# PCB_Instrumenta_o_v2.net
KiCad netlist of a schematic drawn in EAGLE
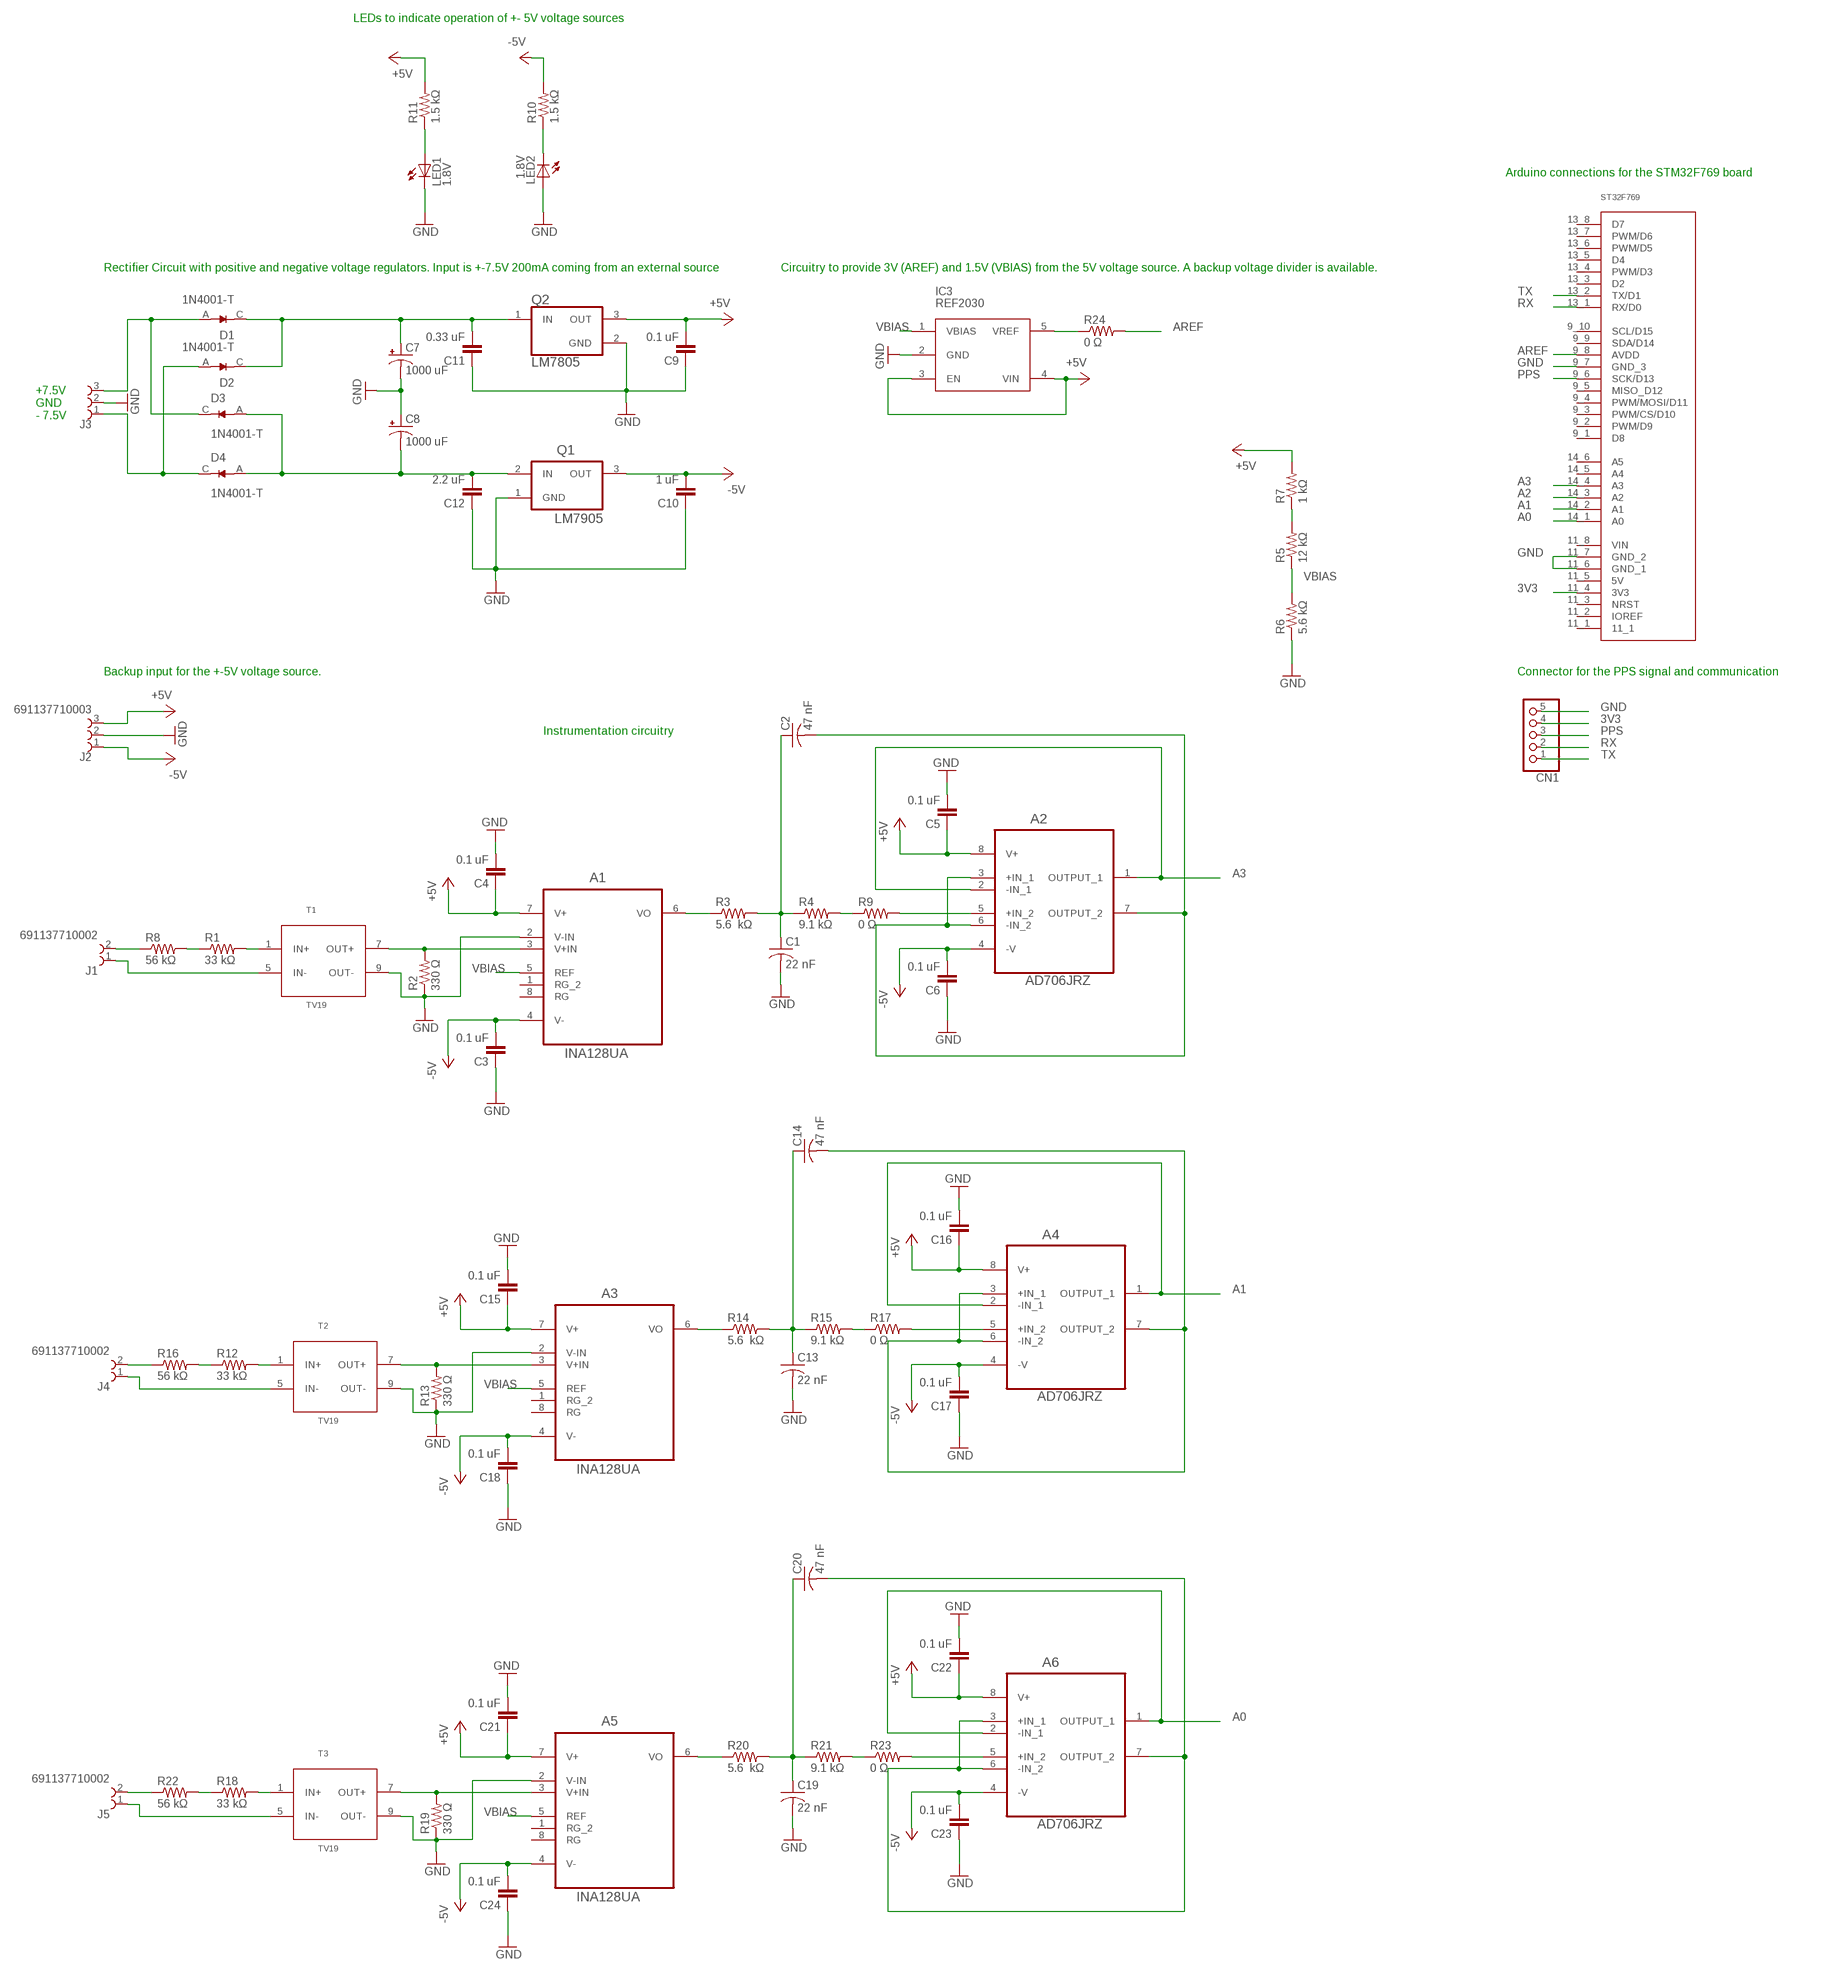
[diagram p0: schematic, sheet 1]

(export (version "E")
  (design (tool "Eeschema 10.0.6"))
  (components
    (comp (ref "A1")
      (value "INA128UA")
      (footprint "eagle-import:SOIC127P600X175-8N")
      (fields (field (name "MF") "Texas"))
      (libsource (lib "eagle-import") (part "INA128UA"))
    )
    (comp (ref "A2")
      (value "AD706JRZ")
      (footprint "eagle-import:SOIC127P600X175-8N")
      (fields (field (name "MF") "Analog Devices") (field (name "MP") "AD706JRZ-REEL7"))
      (libsource (lib "eagle-import") (part "AD706JRZ-REEL-REEL7"))
    )
    (comp (ref "A3")
      (value "INA128UA")
      (footprint "eagle-import:SOIC127P600X175-8N")
      (fields (field (name "MF") "Texas"))
      (libsource (lib "eagle-import") (part "INA128UA"))
    )
    (comp (ref "A4")
      (value "AD706JRZ")
      (footprint "eagle-import:SOIC127P600X175-8N")
      (fields (field (name "MF") "Analog Devices") (field (name "MP") "AD706JRZ-REEL7"))
      (libsource (lib "eagle-import") (part "AD706JRZ-REEL-REEL7"))
    )
    (comp (ref "A5")
      (value "INA128UA")
      (footprint "eagle-import:SOIC127P600X175-8N")
      (fields (field (name "MF") "Texas"))
      (libsource (lib "eagle-import") (part "INA128UA"))
    )
    (comp (ref "A6")
      (value "AD706JRZ")
      (footprint "eagle-import:SOIC127P600X175-8N")
      (fields (field (name "MF") "Analog Devices") (field (name "MP") "AD706JRZ-REEL7"))
      (libsource (lib "eagle-import") (part "AD706JRZ-REEL-REEL7"))
    )
    (comp (ref "C1")
      (value "22 nF")
      (footprint "eagle-import:C1206")
      (libsource (lib "eagle-import") (part "C-USC1206"))
    )
    (comp (ref "C2")
      (value "47 nF")
      (footprint "eagle-import:C1206")
      (libsource (lib "eagle-import") (part "C-USC1206"))
    )
    (comp (ref "C3")
      (value "0.1 uF")
      (footprint "eagle-import:C0805")
      (libsource (lib "eagle-import") (part "C-EUC0805"))
    )
    (comp (ref "C4")
      (value "0.1 uF")
      (footprint "eagle-import:C0805")
      (libsource (lib "eagle-import") (part "C-EUC0805"))
    )
    (comp (ref "C5")
      (value "0.1 uF")
      (footprint "eagle-import:C0805")
      (libsource (lib "eagle-import") (part "C-EUC0805"))
    )
    (comp (ref "C6")
      (value "0.1 uF")
      (footprint "eagle-import:C0805")
      (libsource (lib "eagle-import") (part "C-EUC0805"))
    )
    (comp (ref "C7")
      (value "1000 uF")
      (footprint "eagle-import:E5-10,5")
      (libsource (lib "eagle-import") (part "CPOL-USE5-10.5"))
    )
    (comp (ref "C8")
      (value "1000 uF")
      (footprint "eagle-import:E5-10,5")
      (libsource (lib "eagle-import") (part "CPOL-USE5-10.5"))
    )
    (comp (ref "C9")
      (value "0.1 uF")
      (footprint "eagle-import:C0805")
      (libsource (lib "eagle-import") (part "C-EUC0805"))
    )
    (comp (ref "C10")
      (value "1 uF")
      (footprint "eagle-import:C0805")
      (libsource (lib "eagle-import") (part "C-EUC0805"))
    )
    (comp (ref "C11")
      (value "0.33 uF")
      (footprint "eagle-import:C0805")
      (libsource (lib "eagle-import") (part "C-EUC0805"))
    )
    (comp (ref "C12")
      (value "2.2 uF")
      (footprint "eagle-import:C0805")
      (libsource (lib "eagle-import") (part "C-EUC0805"))
    )
    (comp (ref "C13")
      (value "22 nF")
      (footprint "eagle-import:C1206")
      (libsource (lib "eagle-import") (part "C-USC1206"))
    )
    (comp (ref "C14")
      (value "47 nF")
      (footprint "eagle-import:C1206")
      (libsource (lib "eagle-import") (part "C-USC1206"))
    )
    (comp (ref "C15")
      (value "0.1 uF")
      (footprint "eagle-import:C0805")
      (libsource (lib "eagle-import") (part "C-EUC0805"))
    )
    (comp (ref "C16")
      (value "0.1 uF")
      (footprint "eagle-import:C0805")
      (libsource (lib "eagle-import") (part "C-EUC0805"))
    )
    (comp (ref "C17")
      (value "0.1 uF")
      (footprint "eagle-import:C0805")
      (libsource (lib "eagle-import") (part "C-EUC0805"))
    )
    (comp (ref "C18")
      (value "0.1 uF")
      (footprint "eagle-import:C0805")
      (libsource (lib "eagle-import") (part "C-EUC0805"))
    )
    (comp (ref "C19")
      (value "22 nF")
      (footprint "eagle-import:C1206")
      (libsource (lib "eagle-import") (part "C-USC1206"))
    )
    (comp (ref "C20")
      (value "47 nF")
      (footprint "eagle-import:C1206")
      (libsource (lib "eagle-import") (part "C-USC1206"))
    )
    (comp (ref "C21")
      (value "0.1 uF")
      (footprint "eagle-import:C0805")
      (libsource (lib "eagle-import") (part "C-EUC0805"))
    )
    (comp (ref "C22")
      (value "0.1 uF")
      (footprint "eagle-import:C0805")
      (libsource (lib "eagle-import") (part "C-EUC0805"))
    )
    (comp (ref "C23")
      (value "0.1 uF")
      (footprint "eagle-import:C0805")
      (libsource (lib "eagle-import") (part "C-EUC0805"))
    )
    (comp (ref "C24")
      (value "0.1 uF")
      (footprint "eagle-import:C0805")
      (libsource (lib "eagle-import") (part "C-EUC0805"))
    )
    (comp (ref "CN1")
      (value "PINHD-1X5")
      (footprint "eagle-import:1X05")
      (libsource (lib "eagle-import") (part "PINHD-1X5"))
    )
    (comp (ref "D1")
      (value "1N4001-T")
      (footprint "eagle-import:DIOAD953W69L521D272")
      (fields (field (name "MF") "ON Semiconductor") (field (name "MP") "1N4001"))
      (libsource (lib "eagle-import") (part "1N4001-T"))
    )
    (comp (ref "D2")
      (value "1N4001-T")
      (footprint "eagle-import:DIOAD953W69L521D272")
      (fields (field (name "MF") "ON Semiconductor") (field (name "MP") "1N4001"))
      (libsource (lib "eagle-import") (part "1N4001-T"))
    )
    (comp (ref "D3")
      (value "1N4001-T")
      (footprint "eagle-import:DIOAD953W69L521D272")
      (fields (field (name "MF") "ON Semiconductor") (field (name "MP") "1N4001"))
      (libsource (lib "eagle-import") (part "1N4001-T"))
    )
    (comp (ref "D4")
      (value "1N4001-T")
      (footprint "eagle-import:DIOAD953W69L521D272")
      (fields (field (name "MF") "ON Semiconductor") (field (name "MP") "1N4001"))
      (libsource (lib "eagle-import") (part "1N4001-T"))
    )
    (comp (ref "IC3")
      (value "REF2030")
      (footprint "eagle-import:TSOT-23_S5")
      (libsource (lib "eagle-import") (part "REF2030"))
    )
    (comp (ref "J1")
      (value "691137710002")
      (footprint "eagle-import:691137710002")
      (fields (field (name "MF") "Wurth Electronics"))
      (libsource (lib "eagle-import") (part "691137710002"))
    )
    (comp (ref "J2")
      (value "691137710003")
      (footprint "eagle-import:691137710003")
      (fields (field (name "MF") "Wurth Electronics"))
      (libsource (lib "eagle-import") (part "691137710003"))
    )
    (comp (ref "J3")
      (value "691137710003")
      (footprint "eagle-import:691137710003")
      (fields (field (name "MF") "Wurth Electronics"))
      (libsource (lib "eagle-import") (part "691137710003"))
    )
    (comp (ref "J4")
      (value "691137710002")
      (footprint "eagle-import:691137710002")
      (fields (field (name "MF") "Wurth Electronics"))
      (libsource (lib "eagle-import") (part "691137710002"))
    )
    (comp (ref "J5")
      (value "691137710002")
      (footprint "eagle-import:691137710002")
      (fields (field (name "MF") "Wurth Electronics"))
      (libsource (lib "eagle-import") (part "691137710002"))
    )
    (comp (ref "LED1")
      (value "1.8V")
      (footprint "eagle-import:LED5MM")
      (libsource (lib "eagle-import") (part "my_led_LED5MM"))
    )
    (comp (ref "LED2")
      (value "1.8V")
      (footprint "eagle-import:LED5MM")
      (libsource (lib "eagle-import") (part "LED5MM"))
    )
    (comp (ref "Q1")
      (value "LM7905")
      (footprint "eagle-import:TO254P450X1020X1935-3P")
      (fields (field (name "MF") "STMicroelectronics") (field (name "MP") "L7905ACV"))
      (libsource (lib "eagle-import") (part "L7905ACV"))
    )
    (comp (ref "Q2")
      (value "LM7805")
      (footprint "eagle-import:TO254P1054X470X2600-3")
      (fields (field (name "MF") "ON Semiconductor") (field (name "MP") "LM7805CT"))
      (libsource (lib "eagle-import") (part "LM7805CT/NOPB"))
    )
    (comp (ref "R1")
      (value "33 kΩ")
      (footprint "eagle-import:0207_7")
      (libsource (lib "eagle-import") (part "R-US_0207/7"))
    )
    (comp (ref "R2")
      (value "330 Ω")
      (footprint "eagle-import:0207_7")
      (libsource (lib "eagle-import") (part "R-US_0207/7"))
    )
    (comp (ref "R3")
      (value "5.6 kΩ")
      (footprint "eagle-import:R1206")
      (libsource (lib "eagle-import") (part "resistor_348_R-US_R1206"))
    )
    (comp (ref "R4")
      (value "9.1 kΩ")
      (footprint "eagle-import:R1206")
      (libsource (lib "eagle-import") (part "resistor_348_R-US_R1206"))
    )
    (comp (ref "R5")
      (value "12 kΩ")
      (footprint "eagle-import:R1206")
      (libsource (lib "eagle-import") (part "resistor_348_R-US_R1206"))
    )
    (comp (ref "R6")
      (value "5.6 kΩ")
      (footprint "eagle-import:R1206")
      (libsource (lib "eagle-import") (part "resistor_348_R-US_R1206"))
    )
    (comp (ref "R7")
      (value "1 kΩ")
      (footprint "eagle-import:R1206")
      (libsource (lib "eagle-import") (part "resistor_348_R-US_R1206"))
    )
    (comp (ref "R8")
      (value "56 kΩ")
      (footprint "eagle-import:0207_7")
      (libsource (lib "eagle-import") (part "R-US_0207/7"))
    )
    (comp (ref "R9")
      (value "0 Ω")
      (footprint "eagle-import:R1206")
      (libsource (lib "eagle-import") (part "resistor_348_R-US_R1206"))
    )
    (comp (ref "R10")
      (value "1.5 kΩ")
      (footprint "eagle-import:R1206")
      (libsource (lib "eagle-import") (part "resistor_348_R-US_R1206"))
    )
    (comp (ref "R11")
      (value "1.5 kΩ")
      (footprint "eagle-import:R1206")
      (libsource (lib "eagle-import") (part "resistor_348_R-US_R1206"))
    )
    (comp (ref "R12")
      (value "33 kΩ")
      (footprint "eagle-import:0207_7")
      (libsource (lib "eagle-import") (part "R-US_0207/7"))
    )
    (comp (ref "R13")
      (value "330 Ω")
      (footprint "eagle-import:0207_7")
      (libsource (lib "eagle-import") (part "R-US_0207/7"))
    )
    (comp (ref "R14")
      (value "5.6 kΩ")
      (footprint "eagle-import:R1206")
      (libsource (lib "eagle-import") (part "resistor_348_R-US_R1206"))
    )
    (comp (ref "R15")
      (value "9.1 kΩ")
      (footprint "eagle-import:R1206")
      (libsource (lib "eagle-import") (part "resistor_348_R-US_R1206"))
    )
    (comp (ref "R16")
      (value "56 kΩ")
      (footprint "eagle-import:0207_7")
      (libsource (lib "eagle-import") (part "R-US_0207/7"))
    )
    (comp (ref "R17")
      (value "0 Ω")
      (footprint "eagle-import:R1206")
      (libsource (lib "eagle-import") (part "resistor_348_R-US_R1206"))
    )
    (comp (ref "R18")
      (value "33 kΩ")
      (footprint "eagle-import:0207_7")
      (libsource (lib "eagle-import") (part "R-US_0207/7"))
    )
    (comp (ref "R19")
      (value "330 Ω")
      (footprint "eagle-import:0207_7")
      (libsource (lib "eagle-import") (part "R-US_0207/7"))
    )
    (comp (ref "R20")
      (value "5.6 kΩ")
      (footprint "eagle-import:R1206")
      (libsource (lib "eagle-import") (part "resistor_348_R-US_R1206"))
    )
    (comp (ref "R21")
      (value "9.1 kΩ")
      (footprint "eagle-import:R1206")
      (libsource (lib "eagle-import") (part "resistor_348_R-US_R1206"))
    )
    (comp (ref "R22")
      (value "56 kΩ")
      (footprint "eagle-import:0207_7")
      (libsource (lib "eagle-import") (part "R-US_0207/7"))
    )
    (comp (ref "R23")
      (value "0 Ω")
      (footprint "eagle-import:R1206")
      (libsource (lib "eagle-import") (part "resistor_348_R-US_R1206"))
    )
    (comp (ref "R24")
      (value "0 Ω")
      (footprint "eagle-import:R1206")
      (libsource (lib "eagle-import") (part "resistor_348_R-US_R1206"))
    )
    (comp (ref "T1")
      (value "TV19")
      (footprint "eagle-import:TV19")
      (libsource (lib "eagle-import") (part "TV19"))
    )
    (comp (ref "T2")
      (value "TV19")
      (footprint "eagle-import:TV19")
      (libsource (lib "eagle-import") (part "TV19"))
    )
    (comp (ref "T3")
      (value "TV19")
      (footprint "eagle-import:TV19")
      (libsource (lib "eagle-import") (part "TV19"))
    )
    (comp (ref "U$1")
      (value "ST32F769")
      (footprint "eagle-import:ST32F769")
      (libsource (lib "eagle-import") (part "ST32F769"))
    )
  )
  (nets
    (net (code "1") (name "+5V") (class "Default")
      (node (ref "A1") (pin "7") (pinfunction "V+_7") (pintype "power_in"))
      (node (ref "A2") (pin "8") (pinfunction "V+_8") (pintype "power_in"))
      (node (ref "A3") (pin "7") (pinfunction "V+_7") (pintype "power_in"))
      (node (ref "A4") (pin "8") (pinfunction "V+_8") (pintype "power_in"))
      (node (ref "A5") (pin "7") (pinfunction "V+_7") (pintype "power_in"))
      (node (ref "A6") (pin "8") (pinfunction "V+_8") (pintype "power_in"))
      (node (ref "C15") (pin "1") (pinfunction "1_1") (pintype "passive"))
      (node (ref "C16") (pin "1") (pinfunction "1_1") (pintype "passive"))
      (node (ref "C21") (pin "1") (pinfunction "1_1") (pintype "passive"))
      (node (ref "C22") (pin "1") (pinfunction "1_1") (pintype "passive"))
      (node (ref "C4") (pin "1") (pinfunction "1_1") (pintype "passive"))
      (node (ref "C5") (pin "1") (pinfunction "1_1") (pintype "passive"))
      (node (ref "C9") (pin "2") (pinfunction "2_2") (pintype "passive"))
      (node (ref "IC3") (pin "3") (pinfunction "EN_3") (pintype "bidirectional"))
      (node (ref "IC3") (pin "4") (pinfunction "VIN_4") (pintype "bidirectional"))
      (node (ref "J2") (pin "3") (pinfunction "3_3") (pintype "passive"))
      (node (ref "Q2") (pin "3") (pinfunction "OUT_3") (pintype "output"))
      (node (ref "R11") (pin "2") (pinfunction "2_2") (pintype "passive"))
      (node (ref "R7") (pin "2") (pinfunction "2_2") (pintype "passive"))
    )
    (net (code "2") (name "-5V") (class "Default")
      (node (ref "A1") (pin "4") (pinfunction "V-_4") (pintype "power_in"))
      (node (ref "A2") (pin "4") (pinfunction "-V_4") (pintype "power_in"))
      (node (ref "A3") (pin "4") (pinfunction "V-_4") (pintype "power_in"))
      (node (ref "A4") (pin "4") (pinfunction "-V_4") (pintype "power_in"))
      (node (ref "A5") (pin "4") (pinfunction "V-_4") (pintype "power_in"))
      (node (ref "A6") (pin "4") (pinfunction "-V_4") (pintype "power_in"))
      (node (ref "C10") (pin "2") (pinfunction "2_2") (pintype "passive"))
      (node (ref "C17") (pin "2") (pinfunction "2_2") (pintype "passive"))
      (node (ref "C18") (pin "2") (pinfunction "2_2") (pintype "passive"))
      (node (ref "C23") (pin "2") (pinfunction "2_2") (pintype "passive"))
      (node (ref "C24") (pin "2") (pinfunction "2_2") (pintype "passive"))
      (node (ref "C3") (pin "2") (pinfunction "2_2") (pintype "passive"))
      (node (ref "C6") (pin "2") (pinfunction "2_2") (pintype "passive"))
      (node (ref "J2") (pin "1") (pinfunction "1_1") (pintype "passive"))
      (node (ref "Q1") (pin "3") (pinfunction "OUT_3") (pintype "output"))
      (node (ref "R10") (pin "2") (pinfunction "2_2") (pintype "passive"))
    )
    (net (code "3") (name "/3V3") (class "Default")
      (node (ref "CN1") (pin "4") (pinfunction "4_4") (pintype "passive"))
      (node (ref "U$1") (pin "11_4") (pinfunction "3V3_11_4") (pintype "bidirectional"))
    )
    (net (code "4") (name "/A0") (class "Default")
      (node (ref "A6") (pin "1") (pinfunction "OUTPUT_1_1") (pintype "output"))
      (node (ref "A6") (pin "2") (pinfunction "-IN_1_2") (pintype "input"))
      (node (ref "U$1") (pin "14_1") (pinfunction "A0_14_1") (pintype "bidirectional"))
    )
    (net (code "5") (name "/A1") (class "Default")
      (node (ref "A4") (pin "1") (pinfunction "OUTPUT_1_1") (pintype "output"))
      (node (ref "A4") (pin "2") (pinfunction "-IN_1_2") (pintype "input"))
      (node (ref "U$1") (pin "14_2") (pinfunction "A1_14_2") (pintype "bidirectional"))
    )
    (net (code "6") (name "/A2") (class "Default")
      (node (ref "U$1") (pin "14_3") (pinfunction "A2_14_3") (pintype "bidirectional"))
    )
    (net (code "7") (name "/A3") (class "Default")
      (node (ref "A2") (pin "1") (pinfunction "OUTPUT_1_1") (pintype "output"))
      (node (ref "A2") (pin "2") (pinfunction "-IN_1_2") (pintype "input"))
      (node (ref "U$1") (pin "14_4") (pinfunction "A3_14_4") (pintype "bidirectional"))
    )
    (net (code "8") (name "/AREF") (class "Default")
      (node (ref "R24") (pin "2") (pinfunction "2_2") (pintype "passive"))
      (node (ref "U$1") (pin "9_8") (pinfunction "AVDD_9_8") (pintype "bidirectional"))
    )
    (net (code "9") (name "/PPS") (class "Default")
      (node (ref "CN1") (pin "3") (pinfunction "3_3") (pintype "passive"))
      (node (ref "U$1") (pin "9_6") (pinfunction "SCK/D13_9_6") (pintype "bidirectional"))
    )
    (net (code "10") (name "/RX") (class "Default")
      (node (ref "CN1") (pin "2") (pinfunction "2_2") (pintype "passive"))
      (node (ref "U$1") (pin "13_1") (pinfunction "RX/D0_13_1") (pintype "bidirectional"))
    )
    (net (code "11") (name "/TX") (class "Default")
      (node (ref "CN1") (pin "1") (pinfunction "1_1") (pintype "passive"))
      (node (ref "U$1") (pin "13_2") (pinfunction "TX/D1_13_2") (pintype "bidirectional"))
    )
    (net (code "12") (name "/VBIAS") (class "Default")
      (node (ref "A1") (pin "5") (pinfunction "REF_5") (pintype "input"))
      (node (ref "A3") (pin "5") (pinfunction "REF_5") (pintype "input"))
      (node (ref "A5") (pin "5") (pinfunction "REF_5") (pintype "input"))
      (node (ref "IC3") (pin "1") (pinfunction "VBIAS_1") (pintype "bidirectional"))
      (node (ref "R5") (pin "1") (pinfunction "1_1") (pintype "passive"))
      (node (ref "R6") (pin "2") (pinfunction "2_2") (pintype "passive"))
    )
    (net (code "13") (name "GND") (class "Default")
      (node (ref "A1") (pin "2") (pinfunction "V-IN_2") (pintype "input"))
      (node (ref "A3") (pin "2") (pinfunction "V-IN_2") (pintype "input"))
      (node (ref "A5") (pin "2") (pinfunction "V-IN_2") (pintype "input"))
      (node (ref "C1") (pin "2") (pinfunction "2_2") (pintype "passive"))
      (node (ref "C10") (pin "1") (pinfunction "1_1") (pintype "passive"))
      (node (ref "C11") (pin "1") (pinfunction "1_1") (pintype "passive"))
      (node (ref "C12") (pin "1") (pinfunction "1_1") (pintype "passive"))
      (node (ref "C13") (pin "2") (pinfunction "2_2") (pintype "passive"))
      (node (ref "C15") (pin "2") (pinfunction "2_2") (pintype "passive"))
      (node (ref "C16") (pin "2") (pinfunction "2_2") (pintype "passive"))
      (node (ref "C17") (pin "1") (pinfunction "1_1") (pintype "passive"))
      (node (ref "C18") (pin "1") (pinfunction "1_1") (pintype "passive"))
      (node (ref "C19") (pin "2") (pinfunction "2_2") (pintype "passive"))
      (node (ref "C21") (pin "2") (pinfunction "2_2") (pintype "passive"))
      (node (ref "C22") (pin "2") (pinfunction "2_2") (pintype "passive"))
      (node (ref "C23") (pin "1") (pinfunction "1_1") (pintype "passive"))
      (node (ref "C24") (pin "1") (pinfunction "1_1") (pintype "passive"))
      (node (ref "C3") (pin "1") (pinfunction "1_1") (pintype "passive"))
      (node (ref "C4") (pin "2") (pinfunction "2_2") (pintype "passive"))
      (node (ref "C5") (pin "2") (pinfunction "2_2") (pintype "passive"))
      (node (ref "C6") (pin "1") (pinfunction "1_1") (pintype "passive"))
      (node (ref "C7") (pin "-") (pinfunction "-_-") (pintype "passive"))
      (node (ref "C8") (pin "+") (pinfunction "+_+") (pintype "passive"))
      (node (ref "C9") (pin "1") (pinfunction "1_1") (pintype "passive"))
      (node (ref "CN1") (pin "5") (pinfunction "5_5") (pintype "passive"))
      (node (ref "IC3") (pin "2") (pinfunction "GND_2") (pintype "bidirectional"))
      (node (ref "J2") (pin "2") (pinfunction "2_2") (pintype "passive"))
      (node (ref "J3") (pin "2") (pinfunction "2_2") (pintype "passive"))
      (node (ref "LED1") (pin "K") (pinfunction "C_K") (pintype "passive"))
      (node (ref "LED2") (pin "A") (pinfunction "A_A") (pintype "passive"))
      (node (ref "Q1") (pin "1") (pinfunction "GND_1") (pintype "passive"))
      (node (ref "Q2") (pin "2") (pinfunction "GND_2") (pintype "power_in"))
      (node (ref "R13") (pin "1") (pinfunction "1_1") (pintype "passive"))
      (node (ref "R19") (pin "1") (pinfunction "1_1") (pintype "passive"))
      (node (ref "R2") (pin "1") (pinfunction "1_1") (pintype "passive"))
      (node (ref "R6") (pin "1") (pinfunction "1_1") (pintype "passive"))
      (node (ref "T1") (pin "9") (pinfunction "OUT-_9") (pintype "bidirectional"))
      (node (ref "T2") (pin "9") (pinfunction "OUT-_9") (pintype "bidirectional"))
      (node (ref "T3") (pin "9") (pinfunction "OUT-_9") (pintype "bidirectional"))
      (node (ref "U$1") (pin "11_6") (pinfunction "GND_1_11_6") (pintype "bidirectional"))
      (node (ref "U$1") (pin "11_7") (pinfunction "GND_2_11_7") (pintype "bidirectional"))
      (node (ref "U$1") (pin "9_7") (pinfunction "GND_3_9_7") (pintype "bidirectional"))
    )
    (net (code "14") (name "Net-(A1-V+IN)") (class "Default")
      (node (ref "A1") (pin "3") (pinfunction "V+IN_3") (pintype "input"))
      (node (ref "R2") (pin "2") (pinfunction "2_2") (pintype "passive"))
      (node (ref "T1") (pin "7") (pinfunction "OUT+_7") (pintype "bidirectional"))
    )
    (net (code "15") (name "Net-(A1-VO)") (class "Default")
      (node (ref "A1") (pin "6") (pinfunction "VO_6") (pintype "output"))
      (node (ref "R3") (pin "1") (pinfunction "1_1") (pintype "passive"))
    )
    (net (code "16") (name "Net-(A2-+IN_1)") (class "Default")
      (node (ref "A2") (pin "3") (pinfunction "+IN_1_3") (pintype "input"))
      (node (ref "A2") (pin "6") (pinfunction "-IN_2_6") (pintype "input"))
      (node (ref "A2") (pin "7") (pinfunction "OUTPUT_2_7") (pintype "output"))
      (node (ref "C2") (pin "2") (pinfunction "2_2") (pintype "passive"))
    )
    (net (code "17") (name "Net-(A2-+IN_2)") (class "Default")
      (node (ref "A2") (pin "5") (pinfunction "+IN_2_5") (pintype "input"))
      (node (ref "R9") (pin "2") (pinfunction "2_2") (pintype "passive"))
    )
    (net (code "18") (name "Net-(A3-V+IN)") (class "Default")
      (node (ref "A3") (pin "3") (pinfunction "V+IN_3") (pintype "input"))
      (node (ref "R13") (pin "2") (pinfunction "2_2") (pintype "passive"))
      (node (ref "T2") (pin "7") (pinfunction "OUT+_7") (pintype "bidirectional"))
    )
    (net (code "19") (name "Net-(A3-VO)") (class "Default")
      (node (ref "A3") (pin "6") (pinfunction "VO_6") (pintype "output"))
      (node (ref "R14") (pin "1") (pinfunction "1_1") (pintype "passive"))
    )
    (net (code "20") (name "Net-(A4-+IN_1)") (class "Default")
      (node (ref "A4") (pin "3") (pinfunction "+IN_1_3") (pintype "input"))
      (node (ref "A4") (pin "6") (pinfunction "-IN_2_6") (pintype "input"))
      (node (ref "A4") (pin "7") (pinfunction "OUTPUT_2_7") (pintype "output"))
      (node (ref "C14") (pin "2") (pinfunction "2_2") (pintype "passive"))
    )
    (net (code "21") (name "Net-(A4-+IN_2)") (class "Default")
      (node (ref "A4") (pin "5") (pinfunction "+IN_2_5") (pintype "input"))
      (node (ref "R17") (pin "2") (pinfunction "2_2") (pintype "passive"))
    )
    (net (code "22") (name "Net-(A5-V+IN)") (class "Default")
      (node (ref "A5") (pin "3") (pinfunction "V+IN_3") (pintype "input"))
      (node (ref "R19") (pin "2") (pinfunction "2_2") (pintype "passive"))
      (node (ref "T3") (pin "7") (pinfunction "OUT+_7") (pintype "bidirectional"))
    )
    (net (code "23") (name "Net-(A5-VO)") (class "Default")
      (node (ref "A5") (pin "6") (pinfunction "VO_6") (pintype "output"))
      (node (ref "R20") (pin "1") (pinfunction "1_1") (pintype "passive"))
    )
    (net (code "24") (name "Net-(A6-+IN_1)") (class "Default")
      (node (ref "A6") (pin "3") (pinfunction "+IN_1_3") (pintype "input"))
      (node (ref "A6") (pin "6") (pinfunction "-IN_2_6") (pintype "input"))
      (node (ref "A6") (pin "7") (pinfunction "OUTPUT_2_7") (pintype "output"))
      (node (ref "C20") (pin "2") (pinfunction "2_2") (pintype "passive"))
    )
    (net (code "25") (name "Net-(A6-+IN_2)") (class "Default")
      (node (ref "A6") (pin "5") (pinfunction "+IN_2_5") (pintype "input"))
      (node (ref "R23") (pin "2") (pinfunction "2_2") (pintype "passive"))
    )
    (net (code "26") (name "Net-(C1-Pad1)") (class "Default")
      (node (ref "C1") (pin "1") (pinfunction "1_1") (pintype "passive"))
      (node (ref "C2") (pin "1") (pinfunction "1_1") (pintype "passive"))
      (node (ref "R3") (pin "2") (pinfunction "2_2") (pintype "passive"))
      (node (ref "R4") (pin "1") (pinfunction "1_1") (pintype "passive"))
    )
    (net (code "27") (name "Net-(C13-Pad1)") (class "Default")
      (node (ref "C13") (pin "1") (pinfunction "1_1") (pintype "passive"))
      (node (ref "C14") (pin "1") (pinfunction "1_1") (pintype "passive"))
      (node (ref "R14") (pin "2") (pinfunction "2_2") (pintype "passive"))
      (node (ref "R15") (pin "1") (pinfunction "1_1") (pintype "passive"))
    )
    (net (code "28") (name "Net-(C19-Pad1)") (class "Default")
      (node (ref "C19") (pin "1") (pinfunction "1_1") (pintype "passive"))
      (node (ref "C20") (pin "1") (pinfunction "1_1") (pintype "passive"))
      (node (ref "R20") (pin "2") (pinfunction "2_2") (pintype "passive"))
      (node (ref "R21") (pin "1") (pinfunction "1_1") (pintype "passive"))
    )
    (net (code "29") (name "Net-(D1-PadA)") (class "Default")
      (node (ref "D1") (pin "A") (pinfunction "A_A") (pintype "passive"))
      (node (ref "D3") (pin "C") (pinfunction "C_C") (pintype "passive"))
      (node (ref "J3") (pin "3") (pinfunction "3_3") (pintype "passive"))
    )
    (net (code "30") (name "Net-(D2-PadA)") (class "Default")
      (node (ref "D2") (pin "A") (pinfunction "A_A") (pintype "passive"))
      (node (ref "D4") (pin "C") (pinfunction "C_C") (pintype "passive"))
      (node (ref "J3") (pin "1") (pinfunction "1_1") (pintype "passive"))
    )
    (net (code "31") (name "Net-(IC3-VREF)") (class "Default")
      (node (ref "IC3") (pin "5") (pinfunction "VREF_5") (pintype "bidirectional"))
      (node (ref "R24") (pin "1") (pinfunction "1_1") (pintype "passive"))
    )
    (net (code "32") (name "Net-(J1-Pad2)") (class "Default")
      (node (ref "J1") (pin "2") (pinfunction "2_2") (pintype "passive"))
      (node (ref "R8") (pin "1") (pinfunction "1_1") (pintype "passive"))
    )
    (net (code "33") (name "Net-(J4-Pad2)") (class "Default")
      (node (ref "J4") (pin "2") (pinfunction "2_2") (pintype "passive"))
      (node (ref "R16") (pin "1") (pinfunction "1_1") (pintype "passive"))
    )
    (net (code "34") (name "Net-(J5-Pad2)") (class "Default")
      (node (ref "J5") (pin "2") (pinfunction "2_2") (pintype "passive"))
      (node (ref "R22") (pin "1") (pinfunction "1_1") (pintype "passive"))
    )
    (net (code "35") (name "Net-(LED1-PadA)") (class "Default")
      (node (ref "LED1") (pin "A") (pinfunction "A_A") (pintype "passive"))
      (node (ref "R11") (pin "1") (pinfunction "1_1") (pintype "passive"))
    )
    (net (code "36") (name "Net-(LED2-C)") (class "Default")
      (node (ref "LED2") (pin "K") (pinfunction "C_K") (pintype "passive"))
      (node (ref "R10") (pin "1") (pinfunction "1_1") (pintype "passive"))
    )
    (net (code "37") (name "Net-(Q1-IN)") (class "Default")
      (node (ref "C12") (pin "2") (pinfunction "2_2") (pintype "passive"))
      (node (ref "C8") (pin "-") (pinfunction "-_-") (pintype "passive"))
      (node (ref "D3") (pin "A") (pinfunction "A_A") (pintype "passive"))
      (node (ref "D4") (pin "A") (pinfunction "A_A") (pintype "passive"))
      (node (ref "Q1") (pin "2") (pinfunction "IN_2") (pintype "input"))
    )
    (net (code "38") (name "Net-(Q2-IN)") (class "Default")
      (node (ref "C11") (pin "2") (pinfunction "2_2") (pintype "passive"))
      (node (ref "C7") (pin "+") (pinfunction "+_+") (pintype "passive"))
      (node (ref "D1") (pin "C") (pinfunction "C_C") (pintype "passive"))
      (node (ref "D2") (pin "C") (pinfunction "C_C") (pintype "passive"))
      (node (ref "Q2") (pin "1") (pinfunction "IN_1") (pintype "input"))
    )
    (net (code "39") (name "Net-(R1-Pad1)") (class "Default")
      (node (ref "R1") (pin "1") (pinfunction "1_1") (pintype "passive"))
      (node (ref "R8") (pin "2") (pinfunction "2_2") (pintype "passive"))
    )
    (net (code "40") (name "Net-(R4-Pad2)") (class "Default")
      (node (ref "R4") (pin "2") (pinfunction "2_2") (pintype "passive"))
      (node (ref "R9") (pin "1") (pinfunction "1_1") (pintype "passive"))
    )
    (net (code "41") (name "Net-(R5-Pad2)") (class "Default")
      (node (ref "R5") (pin "2") (pinfunction "2_2") (pintype "passive"))
      (node (ref "R7") (pin "1") (pinfunction "1_1") (pintype "passive"))
    )
    (net (code "42") (name "Net-(R12-Pad1)") (class "Default")
      (node (ref "R12") (pin "1") (pinfunction "1_1") (pintype "passive"))
      (node (ref "R16") (pin "2") (pinfunction "2_2") (pintype "passive"))
    )
    (net (code "43") (name "Net-(R15-Pad2)") (class "Default")
      (node (ref "R15") (pin "2") (pinfunction "2_2") (pintype "passive"))
      (node (ref "R17") (pin "1") (pinfunction "1_1") (pintype "passive"))
    )
    (net (code "44") (name "Net-(R18-Pad1)") (class "Default")
      (node (ref "R18") (pin "1") (pinfunction "1_1") (pintype "passive"))
      (node (ref "R22") (pin "2") (pinfunction "2_2") (pintype "passive"))
    )
    (net (code "45") (name "Net-(R21-Pad2)") (class "Default")
      (node (ref "R21") (pin "2") (pinfunction "2_2") (pintype "passive"))
      (node (ref "R23") (pin "1") (pinfunction "1_1") (pintype "passive"))
    )
    (net (code "46") (name "Net-(T1-IN+)") (class "Default")
      (node (ref "R1") (pin "2") (pinfunction "2_2") (pintype "passive"))
      (node (ref "T1") (pin "1") (pinfunction "IN+_1") (pintype "bidirectional"))
    )
    (net (code "47") (name "Net-(T1-IN-)") (class "Default")
      (node (ref "J1") (pin "1") (pinfunction "1_1") (pintype "passive"))
      (node (ref "T1") (pin "5") (pinfunction "IN-_5") (pintype "bidirectional"))
    )
    (net (code "48") (name "Net-(T2-IN+)") (class "Default")
      (node (ref "R12") (pin "2") (pinfunction "2_2") (pintype "passive"))
      (node (ref "T2") (pin "1") (pinfunction "IN+_1") (pintype "bidirectional"))
    )
    (net (code "49") (name "Net-(T2-IN-)") (class "Default")
      (node (ref "J4") (pin "1") (pinfunction "1_1") (pintype "passive"))
      (node (ref "T2") (pin "5") (pinfunction "IN-_5") (pintype "bidirectional"))
    )
    (net (code "50") (name "Net-(T3-IN+)") (class "Default")
      (node (ref "R18") (pin "2") (pinfunction "2_2") (pintype "passive"))
      (node (ref "T3") (pin "1") (pinfunction "IN+_1") (pintype "bidirectional"))
    )
    (net (code "51") (name "Net-(T3-IN-)") (class "Default")
      (node (ref "J5") (pin "1") (pinfunction "1_1") (pintype "passive"))
      (node (ref "T3") (pin "5") (pinfunction "IN-_5") (pintype "bidirectional"))
    )
    (net (code "52") (name "unconnected-(A1-RG-Pad8)") (class "Default")
      (node (ref "A1") (pin "8") (pinfunction "RG_8") (pintype "input"))
    )
    (net (code "53") (name "unconnected-(A1-RG_2-Pad1)") (class "Default")
      (node (ref "A1") (pin "1") (pinfunction "RG_2_1") (pintype "input"))
    )
    (net (code "54") (name "unconnected-(A3-RG-Pad8)") (class "Default")
      (node (ref "A3") (pin "8") (pinfunction "RG_8") (pintype "input"))
    )
    (net (code "55") (name "unconnected-(A3-RG_2-Pad1)") (class "Default")
      (node (ref "A3") (pin "1") (pinfunction "RG_2_1") (pintype "input"))
    )
    (net (code "56") (name "unconnected-(A5-RG-Pad8)") (class "Default")
      (node (ref "A5") (pin "8") (pinfunction "RG_8") (pintype "input"))
    )
    (net (code "57") (name "unconnected-(A5-RG_2-Pad1)") (class "Default")
      (node (ref "A5") (pin "1") (pinfunction "RG_2_1") (pintype "input"))
    )
    (net (code "58") (name "unconnected-(U$1-5V-Pad11_5)") (class "Default")
      (node (ref "U$1") (pin "11_5") (pinfunction "5V_11_5") (pintype "bidirectional"))
    )
    (net (code "59") (name "unconnected-(U$1-A4-Pad14_5)") (class "Default")
      (node (ref "U$1") (pin "14_5") (pinfunction "A4_14_5") (pintype "bidirectional"))
    )
    (net (code "60") (name "unconnected-(U$1-A5-Pad14_6)") (class "Default")
      (node (ref "U$1") (pin "14_6") (pinfunction "A5_14_6") (pintype "bidirectional"))
    )
    (net (code "61") (name "unconnected-(U$1-D2-Pad13_3)") (class "Default")
      (node (ref "U$1") (pin "13_3") (pinfunction "D2_13_3") (pintype "bidirectional"))
    )
    (net (code "62") (name "unconnected-(U$1-D4-Pad13_5)") (class "Default")
      (node (ref "U$1") (pin "13_5") (pinfunction "D4_13_5") (pintype "bidirectional"))
    )
    (net (code "63") (name "unconnected-(U$1-D7-Pad13_8)") (class "Default")
      (node (ref "U$1") (pin "13_8") (pinfunction "D7_13_8") (pintype "bidirectional"))
    )
    (net (code "64") (name "unconnected-(U$1-D8-Pad9_1)") (class "Default")
      (node (ref "U$1") (pin "9_1") (pinfunction "D8_9_1") (pintype "bidirectional"))
    )
    (net (code "65") (name "unconnected-(U$1-IOREF-Pad11_2)") (class "Default")
      (node (ref "U$1") (pin "11_2") (pinfunction "IOREF_11_2") (pintype "bidirectional"))
    )
    (net (code "66") (name "unconnected-(U$1-MISO_D12-Pad9_5)") (class "Default")
      (node (ref "U$1") (pin "9_5") (pinfunction "MISO_D12_9_5") (pintype "bidirectional"))
    )
    (net (code "67") (name "unconnected-(U$1-NRST-Pad11_3)") (class "Default")
      (node (ref "U$1") (pin "11_3") (pinfunction "NRST_11_3") (pintype "bidirectional"))
    )
    (net (code "68") (name "unconnected-(U$1-PWM{slash}CS{slash}D10-Pad9_3)") (class "Default")
      (node (ref "U$1") (pin "9_3") (pinfunction "PWM/CS/D10_9_3") (pintype "bidirectional"))
    )
    (net (code "69") (name "unconnected-(U$1-PWM{slash}D3-Pad13_4)") (class "Default")
      (node (ref "U$1") (pin "13_4") (pinfunction "PWM/D3_13_4") (pintype "bidirectional"))
    )
    (net (code "70") (name "unconnected-(U$1-PWM{slash}D5-Pad13_6)") (class "Default")
      (node (ref "U$1") (pin "13_6") (pinfunction "PWM/D5_13_6") (pintype "bidirectional"))
    )
    (net (code "71") (name "unconnected-(U$1-PWM{slash}D6-Pad13_7)") (class "Default")
      (node (ref "U$1") (pin "13_7") (pinfunction "PWM/D6_13_7") (pintype "bidirectional"))
    )
    (net (code "72") (name "unconnected-(U$1-PWM{slash}D9-Pad9_2)") (class "Default")
      (node (ref "U$1") (pin "9_2") (pinfunction "PWM/D9_9_2") (pintype "bidirectional"))
    )
    (net (code "73") (name "unconnected-(U$1-PWM{slash}MOSI{slash}D11-Pad9_4)") (class "Default")
      (node (ref "U$1") (pin "9_4") (pinfunction "PWM/MOSI/D11_9_4") (pintype "bidirectional"))
    )
    (net (code "74") (name "unconnected-(U$1-Pad11_1)") (class "Default")
      (node (ref "U$1") (pin "11_1") (pinfunction "11_1_11_1") (pintype "bidirectional"))
    )
    (net (code "75") (name "unconnected-(U$1-SCL{slash}D15-Pad9_10)") (class "Default")
      (node (ref "U$1") (pin "9_10") (pinfunction "SCL/D15_9_10") (pintype "bidirectional"))
    )
    (net (code "76") (name "unconnected-(U$1-SDA{slash}D14-Pad9_9)") (class "Default")
      (node (ref "U$1") (pin "9_9") (pinfunction "SDA/D14_9_9") (pintype "bidirectional"))
    )
    (net (code "77") (name "unconnected-(U$1-VIN-Pad11_8)") (class "Default")
      (node (ref "U$1") (pin "11_8") (pinfunction "VIN_11_8") (pintype "bidirectional"))
    )
  )
)
